# PhoneBLE_v101.net
KiCad netlist of a schematic drawn in Altium Designer
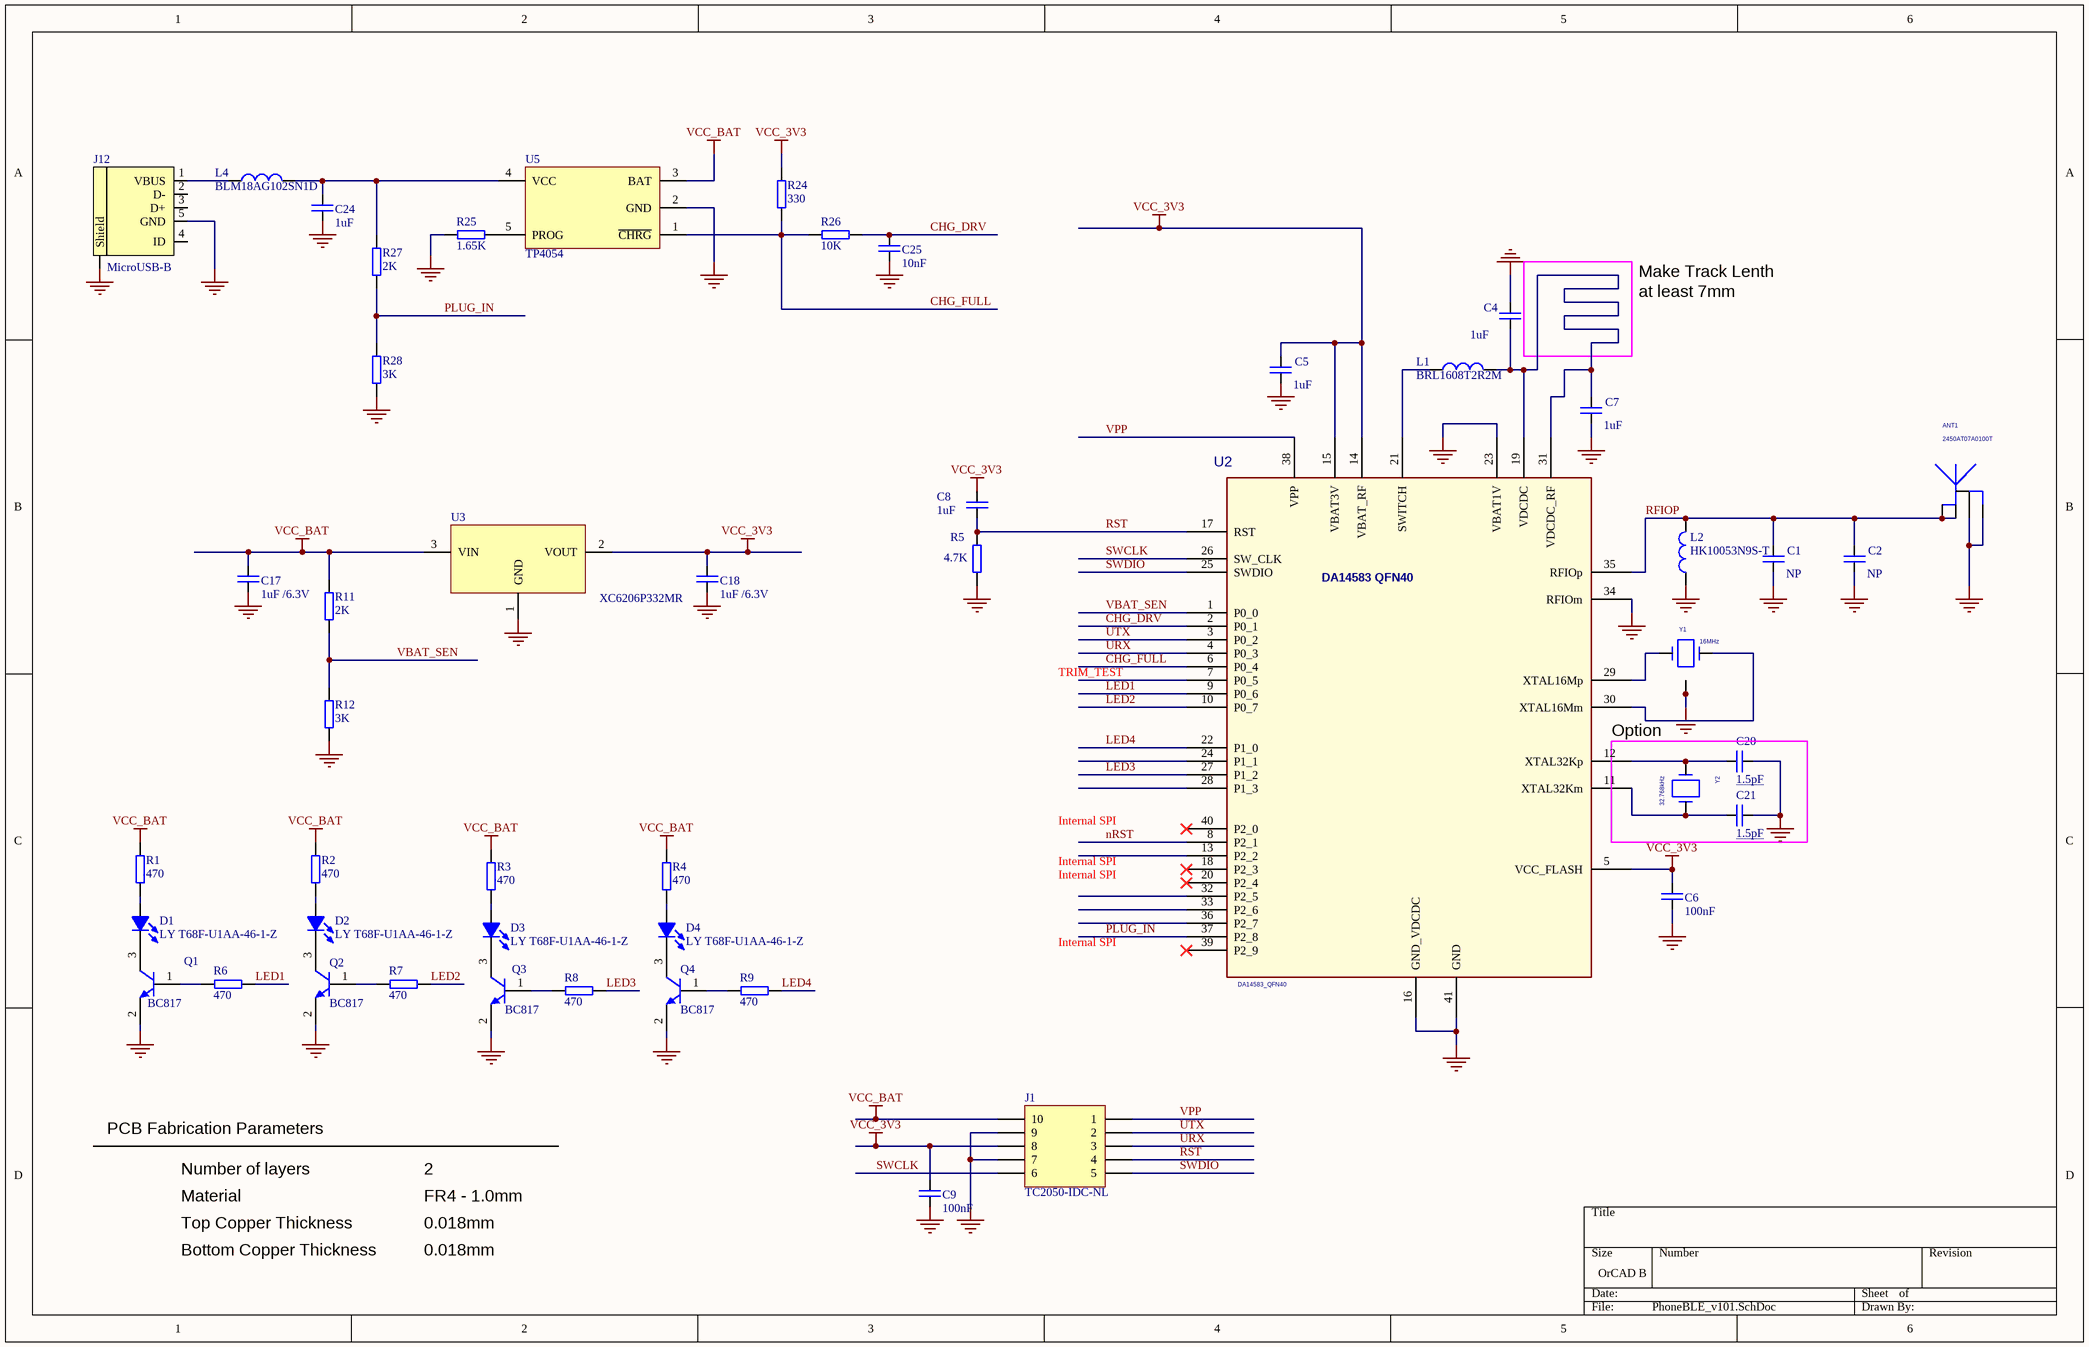
[diagram p0: PhoneBLE_v101.SchDoc]

(export (version "E")
  (design (tool "Eeschema 10.0.6"))
  (components
    (comp (ref "ANT1")
      (value "2450AT07A0100T")
      (footprint "ANT1005")
      (description "Ultra-Miniature 2.4GHz Chip antenna")
      (fields (field (name "MANUFACTURER") "Yageo"))
      (libsource (lib "*") (part "ANTENNA_0"))
    )
    (comp (ref "C1")
      (value "NP")
      (footprint "S_C1005")
      (description "Ceramic Capacitor")
      (libsource (lib "SoftEnc200") (part "CAP-C"))
    )
    (comp (ref "C2")
      (value "NP")
      (footprint "S_C1005")
      (description "Ceramic Capacitor")
      (libsource (lib "SoftEnc200") (part "CAP-C"))
    )
    (comp (ref "C4")
      (value "1uF")
      (footprint "C1005")
      (description "Ceramic Capacitor")
      (libsource (lib "SoftEnc200") (part "CAP-C"))
    )
    (comp (ref "C5")
      (value "1uF")
      (footprint "C1005")
      (description "Ceramic Capacitor")
      (libsource (lib "SoftEnc200") (part "CAP-C"))
    )
    (comp (ref "C6")
      (value "100nF")
      (footprint "C1005")
      (description "Ceramic Capacitor")
      (libsource (lib "SoftEnc200") (part "CAP-C"))
    )
    (comp (ref "C7")
      (value "1uF")
      (footprint "C1005")
      (description "Ceramic Capacitor")
      (libsource (lib "SoftEnc200") (part "CAP-C"))
    )
    (comp (ref "C8")
      (value "1uF")
      (footprint "C1005")
      (description "Ceramic Capacitor")
      (libsource (lib "SoftEnc200") (part "CAP-C"))
    )
    (comp (ref "C9")
      (value "100nF")
      (footprint "C1005")
      (description "Ceramic Capacitor")
      (libsource (lib "SoftEnc200") (part "CAP-C"))
    )
    (comp (ref "C17")
      (value "1uF /6.3V")
      (footprint "C1005")
      (description "Ceramic Capacitor")
      (libsource (lib "SoftEnc200") (part "CAP-C"))
    )
    (comp (ref "C18")
      (value "1uF /6.3V")
      (footprint "C1005")
      (description "Ceramic Capacitor")
      (libsource (lib "SoftEnc200") (part "CAP-C"))
    )
    (comp (ref "C20")
      (value "1.5pF")
      (footprint "C1005")
      (description "Ceramic Capacitor")
      (libsource (lib "SoftEnc200") (part "CAP-C"))
    )
    (comp (ref "C21")
      (value "1.5pF")
      (footprint "C1005")
      (description "Ceramic Capacitor")
      (libsource (lib "SoftEnc200") (part "CAP-C"))
    )
    (comp (ref "C24")
      (value "1uF")
      (footprint "S_C1005")
      (description "Ceramic Capacitor")
      (libsource (lib "SoftEnc200") (part "CAP-C"))
    )
    (comp (ref "C25")
      (value "10nF")
      (footprint "S_C1005")
      (description "Ceramic Capacitor")
      (libsource (lib "SoftEnc200") (part "CAP-C"))
    )
    (comp (ref "D1")
      (value "LY T68F-U1AA-46-1-Z")
      (footprint "T68F_Z")
      (description "LED Lighting Color XLamp? ML-E Red 625nm (620nm ~ 630nm) 4-SMD, J-Lead Exposed Pad")
      (fields (field (name "MFG") "Lumileds"))
      (libsource (lib "Apollonio_Components") (part "Diode_LED"))
    )
    (comp (ref "D2")
      (value "LY T68F-U1AA-46-1-Z")
      (footprint "T68F_Z")
      (description "LED Lighting Color XLamp? ML-E Red 625nm (620nm ~ 630nm) 4-SMD, J-Lead Exposed Pad")
      (fields (field (name "MFG") "Lumileds"))
      (libsource (lib "Apollonio_Components") (part "Diode_LED"))
    )
    (comp (ref "D3")
      (value "LY T68F-U1AA-46-1-Z")
      (footprint "T68F_Z")
      (description "LED Lighting Color XLamp? ML-E Red 625nm (620nm ~ 630nm) 4-SMD, J-Lead Exposed Pad")
      (fields (field (name "MFG") "Lumileds"))
      (libsource (lib "Apollonio_Components") (part "Diode_LED"))
    )
    (comp (ref "D4")
      (value "LY T68F-U1AA-46-1-Z")
      (footprint "T68F_Z")
      (description "LED Lighting Color XLamp? ML-E Red 625nm (620nm ~ 630nm) 4-SMD, J-Lead Exposed Pad")
      (fields (field (name "MFG") "Lumileds"))
      (libsource (lib "Apollonio_Components") (part "Diode_LED"))
    )
    (comp (ref "J1")
      (value "TC2050-IDC-NL")
      (footprint "SMD-10")
      (description "Connector, 10-Pin")
      (libsource (lib "PurpleToothBrush") (part "CONN2X10"))
    )
    (comp (ref "J12")
      (value "MicroUSB-B")
      (footprint "FCI_10118193-0001LF")
      (description "MicroUSB-B-SMT")
      (fields
        (field (name "PART NUMBER") "FCI 10118193-0001LF")
        (field (name "MANUFACTURER") "FCI")
        (field (name "PUBLISHER") "Nordic Semiconductor")
      )
      (libsource (lib "Nordic Passive DB") (part "MiniUSB-AB-SMT"))
    )
    (comp (ref "L1")
      (value "BRL1608T2R2M")
      (footprint "L1608")
      (description "INDUCTOR Power 2.2uH, 500mA, 400MHz")
      (libsource (lib "IT02") (part "Inductor"))
    )
    (comp (ref "L2")
      (value "HK10053N9S-T")
      (footprint "L1005")
      (description "INDUCTOR, 3.9nH")
      (libsource (lib "IT02") (part "Inductor"))
    )
    (comp (ref "L4")
      (value "BLM18AG102SN1D")
      (footprint "S_L1608")
      (description "INDUCTOR Power 2.2uH, 500mA, 400MHz")
      (libsource (lib "IT02") (part "Inductor"))
    )
    (comp (ref "Q1")
      (value "BC817")
      (footprint "SOT-23")
      (description "NPN General Purpose Amplifier")
      (libsource (lib "IT02") (part "BC817"))
    )
    (comp (ref "Q2")
      (value "BC817")
      (footprint "SOT-23")
      (description "NPN General Purpose Amplifier")
      (libsource (lib "IT02") (part "BC817"))
    )
    (comp (ref "Q3")
      (value "BC817")
      (footprint "SOT-23")
      (description "NPN General Purpose Amplifier")
      (libsource (lib "IT02") (part "BC817"))
    )
    (comp (ref "Q4")
      (value "BC817")
      (footprint "SOT-23")
      (description "NPN General Purpose Amplifier")
      (libsource (lib "IT02") (part "BC817"))
    )
    (comp (ref "R1")
      (value "470")
      (footprint "R1005")
      (description "Resistor")
      (libsource (lib "") (part "RES_1"))
    )
    (comp (ref "R2")
      (value "470")
      (footprint "R1005")
      (description "Resistor")
      (libsource (lib "") (part "RES_1"))
    )
    (comp (ref "R3")
      (value "470")
      (footprint "R1005")
      (description "Resistor")
      (libsource (lib "") (part "RES_1"))
    )
    (comp (ref "R4")
      (value "470")
      (footprint "R1005")
      (description "Resistor")
      (libsource (lib "") (part "RES_1"))
    )
    (comp (ref "R5")
      (value "4.7K")
      (footprint "R1005")
      (description "Resistor")
      (libsource (lib "Quard") (part "RES"))
    )
    (comp (ref "R6")
      (value "470")
      (footprint "R1005")
      (description "Resistor")
      (libsource (lib "Quard") (part "RES"))
    )
    (comp (ref "R7")
      (value "470")
      (footprint "R1005")
      (description "Resistor")
      (libsource (lib "Quard") (part "RES"))
    )
    (comp (ref "R8")
      (value "470")
      (footprint "R1005")
      (description "Resistor")
      (libsource (lib "Quard") (part "RES"))
    )
    (comp (ref "R9")
      (value "470")
      (footprint "R1005")
      (description "Resistor")
      (libsource (lib "Quard") (part "RES"))
    )
    (comp (ref "R11")
      (value "2K")
      (footprint "R1005")
      (description "Resistor")
      (libsource (lib "Quard") (part "RES"))
    )
    (comp (ref "R12")
      (value "3K")
      (footprint "R1005")
      (description "Resistor")
      (libsource (lib "Quard") (part "RES"))
    )
    (comp (ref "R24")
      (value "330")
      (footprint "S_R1005")
      (description "Resistor")
      (libsource (lib "Quard") (part "RES"))
    )
    (comp (ref "R25")
      (value "1.65K")
      (footprint "S_R1005")
      (description "Resistor")
      (libsource (lib "Quard") (part "RES"))
    )
    (comp (ref "R26")
      (value "10K")
      (footprint "S_R1005")
      (description "Resistor")
      (libsource (lib "Quard") (part "RES"))
    )
    (comp (ref "R27")
      (value "2K")
      (footprint "S_R1005")
      (description "Resistor")
      (libsource (lib "Quard") (part "RES"))
    )
    (comp (ref "R28")
      (value "3K")
      (footprint "S_R1005")
      (description "Resistor")
      (libsource (lib "Quard") (part "RES"))
    )
    (comp (ref "U2")
      (value "DA14583_QFN40")
      (footprint "QFN40")
      (libsource (lib "*") (part "SC14580_QFN40_1"))
    )
    (comp (ref "U3")
      (value "XC6206P332MR")
      (footprint "SOT-23")
      (description "LDO")
      (libsource (lib "BLENoKey100") (part "XC6206P332MR"))
    )
    (comp (ref "U5")
      (value "TP4054")
      (footprint "SOT23-5")
      (description "Standalone Linear Li-lon Battery Charger with Thermal  Regulation in SOT")
      (libsource (lib "BLENoKey100") (part "TP4054"))
    )
    (comp (ref "Y1")
      (value "16MHz")
      (footprint "SMD2520-4")
      (fields
        (field (name "MANUFACTURER") "NDK")
        (field (name "MANUFACTURER PART NUMBER") "NX2520SA")
        (field (name "PART_NUMBER") "7M-16.000MEEQ-T")
      )
      (libsource (lib "*") (part "CRYSTAL_4PIN"))
    )
    (comp (ref "Y2")
      (value "32.768kHz")
      (footprint "XTAL2012")
      (fields (field (name "PART_NUMBER") "ABS06-32.768KHZ-9-T"))
      (libsource (lib "*") (part "CRYSTAL"))
    )
  )
  (nets
    (net (code "1") (name "/CHG_DRV") (class "Default")
      (node (ref "C25") (pin "2") (pintype "passive"))
      (node (ref "R26") (pin "2") (pintype "passive"))
      (node (ref "U2") (pin "2") (pinfunction "P0_1_2") (pintype "passive"))
    )
    (net (code "2") (name "/CHG_FULL") (class "Default")
      (node (ref "R24") (pin "2") (pintype "passive"))
      (node (ref "R26") (pin "1") (pintype "passive"))
      (node (ref "U2") (pin "6") (pinfunction "P0_4_6") (pintype "passive"))
      (node (ref "U5") (pin "1") (pinfunction "~{CHRG}_1") (pintype "power_in"))
    )
    (net (code "3") (name "/LED1") (class "Default")
      (node (ref "R6") (pin "2") (pintype "passive"))
      (node (ref "U2") (pin "9") (pinfunction "P0_6_9") (pintype "passive"))
    )
    (net (code "4") (name "/LED2") (class "Default")
      (node (ref "R7") (pin "2") (pintype "passive"))
      (node (ref "U2") (pin "10") (pinfunction "P0_7_10") (pintype "passive"))
    )
    (net (code "5") (name "/LED3") (class "Default")
      (node (ref "R8") (pin "2") (pintype "passive"))
      (node (ref "U2") (pin "27") (pinfunction "P1_2_27") (pintype "passive"))
    )
    (net (code "6") (name "/LED4") (class "Default")
      (node (ref "R9") (pin "2") (pintype "passive"))
      (node (ref "U2") (pin "22") (pinfunction "P1_0_22") (pintype "passive"))
    )
    (net (code "7") (name "/PLUG_IN") (class "Default")
      (node (ref "R27") (pin "1") (pintype "passive"))
      (node (ref "R28") (pin "2") (pintype "passive"))
      (node (ref "U2") (pin "37") (pinfunction "P2_8_37") (pintype "passive"))
    )
    (net (code "8") (name "/RFIOP") (class "Default")
      (node (ref "ANT1") (pin "1") (pinfunction "FEED1_1") (pintype "passive"))
      (node (ref "ANT1") (pin "4") (pinfunction "FEED2_4") (pintype "passive"))
      (node (ref "C1") (pin "2") (pintype "passive"))
      (node (ref "C2") (pin "2") (pintype "passive"))
      (node (ref "L2") (pin "2") (pinfunction "2_2") (pintype "passive"))
      (node (ref "U2") (pin "35") (pinfunction "RFIOp_35") (pintype "passive"))
    )
    (net (code "9") (name "/RST") (class "Default")
      (node (ref "C8") (pin "1") (pintype "passive"))
      (node (ref "J1") (pin "4") (pinfunction "4_4") (pintype "passive"))
      (node (ref "R5") (pin "2") (pintype "passive"))
      (node (ref "U2") (pin "17") (pinfunction "RST_17") (pintype "passive"))
    )
    (net (code "10") (name "/SWCLK") (class "Default")
      (node (ref "J1") (pin "6") (pinfunction "6_6") (pintype "passive"))
      (node (ref "U2") (pin "26") (pinfunction "SW_CLK_26") (pintype "passive"))
    )
    (net (code "11") (name "/SWDIO") (class "Default")
      (node (ref "J1") (pin "5") (pinfunction "5_5") (pintype "passive"))
      (node (ref "U2") (pin "25") (pinfunction "SWDIO_25") (pintype "passive"))
    )
    (net (code "12") (name "/URX") (class "Default")
      (node (ref "J1") (pin "3") (pinfunction "3_3") (pintype "passive"))
      (node (ref "U2") (pin "4") (pinfunction "P0_3_4") (pintype "passive"))
    )
    (net (code "13") (name "/UTX") (class "Default")
      (node (ref "J1") (pin "2") (pinfunction "2_2") (pintype "passive"))
      (node (ref "U2") (pin "3") (pinfunction "P0_2_3") (pintype "passive"))
    )
    (net (code "14") (name "/VBAT_SEN") (class "Default")
      (node (ref "R11") (pin "1") (pintype "passive"))
      (node (ref "R12") (pin "2") (pintype "passive"))
      (node (ref "U2") (pin "1") (pinfunction "P0_0_1") (pintype "passive"))
    )
    (net (code "15") (name "/VPP") (class "Default")
      (node (ref "J1") (pin "1") (pinfunction "1_1") (pintype "passive"))
      (node (ref "U2") (pin "38") (pinfunction "VPP_38") (pintype "passive"))
    )
    (net (code "16") (name "/nRST") (class "Default")
      (node (ref "U2") (pin "8") (pinfunction "P2_1_8") (pintype "passive"))
    )
    (net (code "17") (name "GND") (class "Default")
      (node (ref "ANT1") (pin "2") (pinfunction "GNDANT1_2") (pintype "passive"))
      (node (ref "ANT1") (pin "3") (pinfunction "GNDANT2_3") (pintype "passive"))
      (node (ref "C1") (pin "1") (pintype "passive"))
      (node (ref "C17") (pin "1") (pintype "passive"))
      (node (ref "C18") (pin "1") (pintype "passive"))
      (node (ref "C2") (pin "1") (pintype "passive"))
      (node (ref "C20") (pin "1") (pintype "passive"))
      (node (ref "C21") (pin "1") (pintype "passive"))
      (node (ref "C24") (pin "1") (pintype "passive"))
      (node (ref "C25") (pin "1") (pintype "passive"))
      (node (ref "C4") (pin "2") (pintype "passive"))
      (node (ref "C5") (pin "1") (pintype "passive"))
      (node (ref "C6") (pin "1") (pintype "passive"))
      (node (ref "C7") (pin "1") (pintype "passive"))
      (node (ref "C9") (pin "1") (pintype "passive"))
      (node (ref "J1") (pin "7") (pinfunction "7_7") (pintype "passive"))
      (node (ref "J1") (pin "9") (pinfunction "9_9") (pintype "passive"))
      (node (ref "J12") (pin "5") (pinfunction "GND_5") (pintype "power_in"))
      (node (ref "J12") (pin "6") (pinfunction "Shield_6") (pintype "power_in"))
      (node (ref "L2") (pin "1") (pinfunction "1_1") (pintype "passive"))
      (node (ref "Q1") (pin "2") (pinfunction "E_2") (pintype "passive"))
      (node (ref "Q2") (pin "2") (pinfunction "E_2") (pintype "passive"))
      (node (ref "Q3") (pin "2") (pinfunction "E_2") (pintype "passive"))
      (node (ref "Q4") (pin "2") (pinfunction "E_2") (pintype "passive"))
      (node (ref "R12") (pin "1") (pintype "passive"))
      (node (ref "R25") (pin "2") (pintype "passive"))
      (node (ref "R28") (pin "1") (pintype "passive"))
      (node (ref "R5") (pin "1") (pintype "passive"))
      (node (ref "U2") (pin "16") (pinfunction "GND_VDCDC_16") (pintype "passive"))
      (node (ref "U2") (pin "23") (pinfunction "VBAT1V_23") (pintype "passive"))
      (node (ref "U2") (pin "34") (pinfunction "RFIOm_34") (pintype "passive"))
      (node (ref "U2") (pin "41") (pinfunction "GND_41") (pintype "passive"))
      (node (ref "U3") (pin "1") (pinfunction "GND_1") (pintype "power_in"))
      (node (ref "U5") (pin "2") (pinfunction "GND_2") (pintype "power_in"))
      (node (ref "Y1") (pin "2") (pinfunction "2_2") (pintype "passive"))
      (node (ref "Y1") (pin "4") (pinfunction "4_4") (pintype "passive"))
    )
    (net (code "18") (name "Net-(D1-PadA)") (class "Default")
      (node (ref "D1") (pin "A") (pinfunction "A_A") (pintype "passive"))
      (node (ref "R1") (pin "2") (pintype "passive"))
    )
    (net (code "19") (name "Net-(D2-PadA)") (class "Default")
      (node (ref "D2") (pin "A") (pinfunction "A_A") (pintype "passive"))
      (node (ref "R2") (pin "2") (pintype "passive"))
    )
    (net (code "20") (name "Net-(D3-PadA)") (class "Default")
      (node (ref "D3") (pin "A") (pinfunction "A_A") (pintype "passive"))
      (node (ref "R3") (pin "2") (pintype "passive"))
    )
    (net (code "21") (name "Net-(D4-PadA)") (class "Default")
      (node (ref "D4") (pin "A") (pinfunction "A_A") (pintype "passive"))
      (node (ref "R4") (pin "2") (pintype "passive"))
    )
    (net (code "22") (name "Net-(J12-VBUS)") (class "Default")
      (node (ref "J12") (pin "1") (pinfunction "VBUS_1") (pintype "power_in"))
      (node (ref "L4") (pin "1") (pinfunction "1_1") (pintype "passive"))
    )
    (net (code "23") (name "Net-(Q1-B)") (class "Default")
      (node (ref "Q1") (pin "1") (pinfunction "B_1") (pintype "passive"))
      (node (ref "R6") (pin "1") (pintype "passive"))
    )
    (net (code "24") (name "Net-(Q1-C)") (class "Default")
      (node (ref "D1") (pin "K") (pinfunction "K_K") (pintype "passive"))
      (node (ref "Q1") (pin "3") (pinfunction "C_3") (pintype "passive"))
    )
    (net (code "25") (name "Net-(Q2-B)") (class "Default")
      (node (ref "Q2") (pin "1") (pinfunction "B_1") (pintype "passive"))
      (node (ref "R7") (pin "1") (pintype "passive"))
    )
    (net (code "26") (name "Net-(Q2-C)") (class "Default")
      (node (ref "D2") (pin "K") (pinfunction "K_K") (pintype "passive"))
      (node (ref "Q2") (pin "3") (pinfunction "C_3") (pintype "passive"))
    )
    (net (code "27") (name "Net-(Q3-B)") (class "Default")
      (node (ref "Q3") (pin "1") (pinfunction "B_1") (pintype "passive"))
      (node (ref "R8") (pin "1") (pintype "passive"))
    )
    (net (code "28") (name "Net-(Q3-C)") (class "Default")
      (node (ref "D3") (pin "K") (pinfunction "K_K") (pintype "passive"))
      (node (ref "Q3") (pin "3") (pinfunction "C_3") (pintype "passive"))
    )
    (net (code "29") (name "Net-(Q4-B)") (class "Default")
      (node (ref "Q4") (pin "1") (pinfunction "B_1") (pintype "passive"))
      (node (ref "R9") (pin "1") (pintype "passive"))
    )
    (net (code "30") (name "Net-(Q4-C)") (class "Default")
      (node (ref "D4") (pin "K") (pinfunction "K_K") (pintype "passive"))
      (node (ref "Q4") (pin "3") (pinfunction "C_3") (pintype "passive"))
    )
    (net (code "31") (name "Net-(U2-SWITCH)") (class "Default")
      (node (ref "L1") (pin "1") (pinfunction "1_1") (pintype "passive"))
      (node (ref "U2") (pin "21") (pinfunction "SWITCH_21") (pintype "passive"))
    )
    (net (code "32") (name "Net-(U2-VDCDC)") (class "Default")
      (node (ref "C4") (pin "1") (pintype "passive"))
      (node (ref "C7") (pin "2") (pintype "passive"))
      (node (ref "L1") (pin "2") (pinfunction "2_2") (pintype "passive"))
      (node (ref "U2") (pin "19") (pinfunction "VDCDC_19") (pintype "passive"))
      (node (ref "U2") (pin "31") (pinfunction "VDCDC_RF_31") (pintype "passive"))
    )
    (net (code "33") (name "Net-(U2-XTAL16Mm)") (class "Default")
      (node (ref "U2") (pin "30") (pinfunction "XTAL16Mm_30") (pintype "passive"))
      (node (ref "Y1") (pin "3") (pinfunction "3_3") (pintype "passive"))
    )
    (net (code "34") (name "Net-(U2-XTAL16Mp)") (class "Default")
      (node (ref "U2") (pin "29") (pinfunction "XTAL16Mp_29") (pintype "passive"))
      (node (ref "Y1") (pin "1") (pinfunction "1_1") (pintype "passive"))
    )
    (net (code "35") (name "Net-(U2-XTAL32Km)") (class "Default")
      (node (ref "C21") (pin "2") (pintype "passive"))
      (node (ref "U2") (pin "11") (pinfunction "XTAL32Km_11") (pintype "passive"))
      (node (ref "Y2") (pin "2") (pinfunction "2_2") (pintype "passive"))
    )
    (net (code "36") (name "Net-(U2-XTAL32Kp)") (class "Default")
      (node (ref "C20") (pin "2") (pintype "passive"))
      (node (ref "U2") (pin "12") (pinfunction "XTAL32Kp_12") (pintype "passive"))
      (node (ref "Y2") (pin "1") (pinfunction "1_1") (pintype "passive"))
    )
    (net (code "37") (name "Net-(U5-PROG)") (class "Default")
      (node (ref "R25") (pin "1") (pintype "passive"))
      (node (ref "U5") (pin "5") (pinfunction "PROG_5") (pintype "power_in"))
    )
    (net (code "38") (name "Net-(U5-VCC)") (class "Default")
      (node (ref "C24") (pin "2") (pintype "passive"))
      (node (ref "L4") (pin "2") (pinfunction "2_2") (pintype "passive"))
      (node (ref "R27") (pin "2") (pintype "passive"))
      (node (ref "U5") (pin "4") (pinfunction "VCC_4") (pintype "power_in"))
    )
    (net (code "39") (name "VCC_3V3") (class "Default")
      (node (ref "C18") (pin "2") (pintype "passive"))
      (node (ref "C5") (pin "2") (pintype "passive"))
      (node (ref "C6") (pin "2") (pintype "passive"))
      (node (ref "C8") (pin "2") (pintype "passive"))
      (node (ref "C9") (pin "2") (pintype "passive"))
      (node (ref "J1") (pin "8") (pinfunction "8_8") (pintype "passive"))
      (node (ref "R24") (pin "1") (pintype "passive"))
      (node (ref "U2") (pin "14") (pinfunction "VBAT_RF_14") (pintype "passive"))
      (node (ref "U2") (pin "15") (pinfunction "VBAT3V_15") (pintype "passive"))
      (node (ref "U2") (pin "5") (pinfunction "VCC_FLASH_5") (pintype "passive"))
      (node (ref "U3") (pin "2") (pinfunction "VOUT_2") (pintype "power_in"))
    )
    (net (code "40") (name "VCC_BAT") (class "Default")
      (node (ref "C17") (pin "2") (pintype "passive"))
      (node (ref "J1") (pin "10") (pinfunction "10_10") (pintype "passive"))
      (node (ref "R1") (pin "1") (pintype "passive"))
      (node (ref "R11") (pin "2") (pintype "passive"))
      (node (ref "R2") (pin "1") (pintype "passive"))
      (node (ref "R3") (pin "1") (pintype "passive"))
      (node (ref "R4") (pin "1") (pintype "passive"))
      (node (ref "U3") (pin "3") (pinfunction "VIN_3") (pintype "power_in"))
      (node (ref "U5") (pin "3") (pinfunction "BAT_3") (pintype "power_in"))
    )
    (net (code "41") (name "unconnected-(J12-D+-Pad3)") (class "Default")
      (node (ref "J12") (pin "3") (pinfunction "D+_3") (pintype "passive"))
    )
    (net (code "42") (name "unconnected-(J12-D--Pad2)") (class "Default")
      (node (ref "J12") (pin "2") (pinfunction "D-_2") (pintype "passive"))
    )
    (net (code "43") (name "unconnected-(J12-ID-Pad4)") (class "Default")
      (node (ref "J12") (pin "4") (pinfunction "ID_4") (pintype "passive"))
    )
    (net (code "44") (name "unconnected-(U2-P0_5-Pad7)") (class "Default")
      (node (ref "U2") (pin "7") (pinfunction "P0_5_7") (pintype "passive"))
    )
    (net (code "45") (name "unconnected-(U2-P1_1-Pad24)") (class "Default")
      (node (ref "U2") (pin "24") (pinfunction "P1_1_24") (pintype "passive"))
    )
    (net (code "46") (name "unconnected-(U2-P1_3-Pad28)") (class "Default")
      (node (ref "U2") (pin "28") (pinfunction "P1_3_28") (pintype "passive"))
    )
    (net (code "47") (name "unconnected-(U2-P2_0-Pad40)") (class "Default")
      (node (ref "U2") (pin "40") (pinfunction "P2_0_40") (pintype "passive+no_connect"))
    )
    (net (code "48") (name "unconnected-(U2-P2_2-Pad13)") (class "Default")
      (node (ref "U2") (pin "13") (pinfunction "P2_2_13") (pintype "passive"))
    )
    (net (code "49") (name "unconnected-(U2-P2_3-Pad18)") (class "Default")
      (node (ref "U2") (pin "18") (pinfunction "P2_3_18") (pintype "passive+no_connect"))
    )
    (net (code "50") (name "unconnected-(U2-P2_4-Pad20)") (class "Default")
      (node (ref "U2") (pin "20") (pinfunction "P2_4_20") (pintype "passive+no_connect"))
    )
    (net (code "51") (name "unconnected-(U2-P2_5-Pad32)") (class "Default")
      (node (ref "U2") (pin "32") (pinfunction "P2_5_32") (pintype "passive"))
    )
    (net (code "52") (name "unconnected-(U2-P2_6-Pad33)") (class "Default")
      (node (ref "U2") (pin "33") (pinfunction "P2_6_33") (pintype "passive"))
    )
    (net (code "53") (name "unconnected-(U2-P2_7-Pad36)") (class "Default")
      (node (ref "U2") (pin "36") (pinfunction "P2_7_36") (pintype "passive"))
    )
    (net (code "54") (name "unconnected-(U2-P2_9-Pad39)") (class "Default")
      (node (ref "U2") (pin "39") (pinfunction "P2_9_39") (pintype "passive+no_connect"))
    )
  )
)
